# Sheet1.net
KiCad netlist of a schematic drawn in Altium Designer
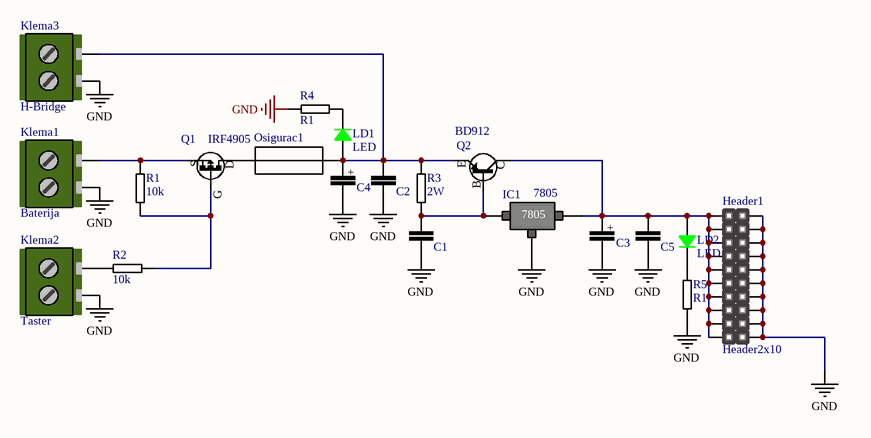
[diagram p0: Sheet1.SchDoc]

(export (version "E")
  (design (tool "Eeschema 10.0.6"))
  (components
    (comp (ref "C1") (value "C1") (footprint "C1(ceramic)") (libsource (lib "KILEX LIB SCH") (part "C1")))
    (comp (ref "C2") (value "C1") (footprint "C1(ceramic)") (libsource (lib "KILEX LIB SCH") (part "C1")))
    (comp (ref "C3") (value "C2") (footprint "C2(elektrolit)") (libsource (lib "KILEX LIB SCH") (part "C2")))
    (comp (ref "C4") (value "C2") (footprint "C2(elektrolit)") (libsource (lib "KILEX LIB SCH") (part "C2")))
    (comp (ref "C5") (value "C1") (footprint "C1(ceramic)") (libsource (lib "KILEX LIB SCH") (part "C1")))
    (comp (ref "Header1")
      (value "Header2x10")
      (footprint "HEADER2x10")
      (libsource (lib "KILEX LIB SCH") (part "Header2x10"))
    )
    (comp (ref "IC1")
      (value "7805")
      (footprint "TO220_Savijeni")
      (libsource (lib "KILEX LIB SCH") (part "7805"))
    )
    (comp (ref "Klema1")
      (value "Baterija")
      (footprint "Klema")
      (libsource (lib "KILEX LIB SCH") (part "Klema"))
    )
    (comp (ref "Klema2")
      (value "Taster")
      (footprint "Klema")
      (libsource (lib "KILEX LIB SCH") (part "Klema"))
    )
    (comp (ref "Klema3")
      (value "H-Bridge")
      (footprint "Klema")
      (libsource (lib "KILEX LIB SCH") (part "Klema"))
    )
    (comp (ref "LD1") (value "LED") (footprint "LED(3mm)") (libsource (lib "KILEX LIB SCH") (part "LED")))
    (comp (ref "LD2") (value "LED") (footprint "LED(3mm)") (libsource (lib "KILEX LIB SCH") (part "LED")))
    (comp (ref "Osigurac1")
      (value "FUSE")
      (footprint "Osigurac")
      (libsource (lib "KILEX LIB SCH") (part "FUSE"))
    )
    (comp (ref "Q1")
      (value "IRF4905")
      (footprint "TO220_Savijeni")
      (libsource (lib "KILEX LIB SCH") (part "P-Channel MOSFET"))
    )
    (comp (ref "Q2")
      (value "BD912")
      (footprint "TO220_Savijeni")
      (libsource (lib "KILEX LIB SCH") (part "Transistor PNP"))
    )
    (comp (ref "R1") (value "10k") (footprint "R1(300milsa)") (libsource (lib "KILEX LIB SCH") (part "R1")))
    (comp (ref "R2") (value "10k") (footprint "R1(300milsa)") (libsource (lib "KILEX LIB SCH") (part "R1")))
    (comp (ref "R3") (value "2W") (footprint "R1(2W)") (libsource (lib "KILEX LIB SCH") (part "R1")))
    (comp (ref "R4") (value "R1") (footprint "R1(300milsa)") (libsource (lib "KILEX LIB SCH") (part "R1")))
    (comp (ref "R5") (value "R1") (footprint "R1(300milsa)") (libsource (lib "KILEX LIB SCH") (part "R1")))
  )
  (nets
    (net (code "1") (name "GND") (class "Default")
      (node (ref "C1") (pin "1") (pinfunction "1_1") (pintype "passive"))
      (node (ref "C2") (pin "2") (pinfunction "2_2") (pintype "passive"))
      (node (ref "C3") (pin "2") (pinfunction "2_2") (pintype "passive"))
      (node (ref "C4") (pin "2") (pinfunction "2_2") (pintype "passive"))
      (node (ref "C5") (pin "2") (pinfunction "2_2") (pintype "passive"))
      (node (ref "Header1") (pin "10") (pinfunction "10_10") (pintype "passive"))
      (node (ref "Header1") (pin "12") (pinfunction "12_12") (pintype "passive"))
      (node (ref "Header1") (pin "14") (pinfunction "14_14") (pintype "passive"))
      (node (ref "Header1") (pin "16") (pinfunction "16_16") (pintype "passive"))
      (node (ref "Header1") (pin "18") (pinfunction "18_18") (pintype "passive"))
      (node (ref "Header1") (pin "2") (pinfunction "2_2") (pintype "passive"))
      (node (ref "Header1") (pin "20") (pinfunction "20_20") (pintype "passive"))
      (node (ref "Header1") (pin "4") (pinfunction "4_4") (pintype "passive"))
      (node (ref "Header1") (pin "6") (pinfunction "6_6") (pintype "passive"))
      (node (ref "Header1") (pin "8") (pinfunction "8_8") (pintype "passive"))
      (node (ref "IC1") (pin "2") (pinfunction "2_2") (pintype "passive"))
      (node (ref "Klema1") (pin "1") (pinfunction "1_1") (pintype "passive"))
      (node (ref "Klema2") (pin "1") (pinfunction "1_1") (pintype "passive"))
      (node (ref "Klema3") (pin "1") (pinfunction "1_1") (pintype "passive"))
      (node (ref "R4") (pin "1") (pinfunction "1_1") (pintype "passive"))
      (node (ref "R5") (pin "1") (pinfunction "1_1") (pintype "passive"))
    )
    (net (code "2") (name "Net-(C1-Pad2)") (class "Default")
      (node (ref "C1") (pin "2") (pinfunction "2_2") (pintype "passive"))
      (node (ref "IC1") (pin "1") (pinfunction "1_1") (pintype "passive"))
      (node (ref "Q2") (pin "1") (pinfunction "1_1") (pintype "passive"))
      (node (ref "R3") (pin "2") (pinfunction "2_2") (pintype "passive"))
    )
    (net (code "3") (name "Net-(C2-Pad1)") (class "Default")
      (node (ref "C2") (pin "1") (pinfunction "1_1") (pintype "passive"))
      (node (ref "C4") (pin "1") (pinfunction "1_1") (pintype "passive"))
      (node (ref "Klema3") (pin "2") (pinfunction "2_2") (pintype "passive"))
      (node (ref "LD1") (pin "1") (pinfunction "1_1") (pintype "passive"))
      (node (ref "Osigurac1") (pin "2") (pinfunction "2_2") (pintype "passive"))
      (node (ref "Q2") (pin "2") (pinfunction "2_2") (pintype "passive"))
      (node (ref "R3") (pin "1") (pinfunction "1_1") (pintype "passive"))
    )
    (net (code "4") (name "Net-(C3-Pad1)") (class "Default")
      (node (ref "C3") (pin "1") (pinfunction "1_1") (pintype "passive"))
      (node (ref "C5") (pin "1") (pinfunction "1_1") (pintype "passive"))
      (node (ref "Header1") (pin "1") (pinfunction "1_1") (pintype "passive"))
      (node (ref "Header1") (pin "11") (pinfunction "11_11") (pintype "passive"))
      (node (ref "Header1") (pin "13") (pinfunction "13_13") (pintype "passive"))
      (node (ref "Header1") (pin "15") (pinfunction "15_15") (pintype "passive"))
      (node (ref "Header1") (pin "17") (pinfunction "17_17") (pintype "passive"))
      (node (ref "Header1") (pin "19") (pinfunction "19_19") (pintype "passive"))
      (node (ref "Header1") (pin "3") (pinfunction "3_3") (pintype "passive"))
      (node (ref "Header1") (pin "5") (pinfunction "5_5") (pintype "passive"))
      (node (ref "Header1") (pin "7") (pinfunction "7_7") (pintype "passive"))
      (node (ref "Header1") (pin "9") (pinfunction "9_9") (pintype "passive"))
      (node (ref "IC1") (pin "3") (pinfunction "3_3") (pintype "passive"))
      (node (ref "LD2") (pin "1") (pinfunction "1_1") (pintype "passive"))
      (node (ref "Q2") (pin "3") (pinfunction "3_3") (pintype "passive"))
    )
    (net (code "5") (name "Net-(Klema1-Pad2)") (class "Default")
      (node (ref "Klema1") (pin "2") (pinfunction "2_2") (pintype "passive"))
      (node (ref "Q1") (pin "3") (pinfunction "3_3") (pintype "passive"))
      (node (ref "R1") (pin "2") (pinfunction "2_2") (pintype "passive"))
    )
    (net (code "6") (name "Net-(Klema2-Pad2)") (class "Default")
      (node (ref "Klema2") (pin "2") (pinfunction "2_2") (pintype "passive"))
      (node (ref "R2") (pin "2") (pinfunction "2_2") (pintype "passive"))
    )
    (net (code "7") (name "Net-(LD1-Pad2)") (class "Default")
      (node (ref "LD1") (pin "2") (pinfunction "2_2") (pintype "passive"))
      (node (ref "R4") (pin "2") (pinfunction "2_2") (pintype "passive"))
    )
    (net (code "8") (name "Net-(LD2-Pad2)") (class "Default")
      (node (ref "LD2") (pin "2") (pinfunction "2_2") (pintype "passive"))
      (node (ref "R5") (pin "2") (pinfunction "2_2") (pintype "passive"))
    )
    (net (code "9") (name "Net-(Osigurac1-Pad1)") (class "Default")
      (node (ref "Osigurac1") (pin "1") (pinfunction "1_1") (pintype "passive"))
      (node (ref "Q1") (pin "2") (pinfunction "2_2") (pintype "passive"))
    )
    (net (code "10") (name "Net-(Q1-Pad1)") (class "Default")
      (node (ref "Q1") (pin "1") (pinfunction "1_1") (pintype "passive"))
      (node (ref "R1") (pin "1") (pinfunction "1_1") (pintype "passive"))
      (node (ref "R2") (pin "1") (pinfunction "1_1") (pintype "passive"))
    )
  )
)
